# module-basic-ui.net
KiCad netlist of a schematic drawn in EAGLE
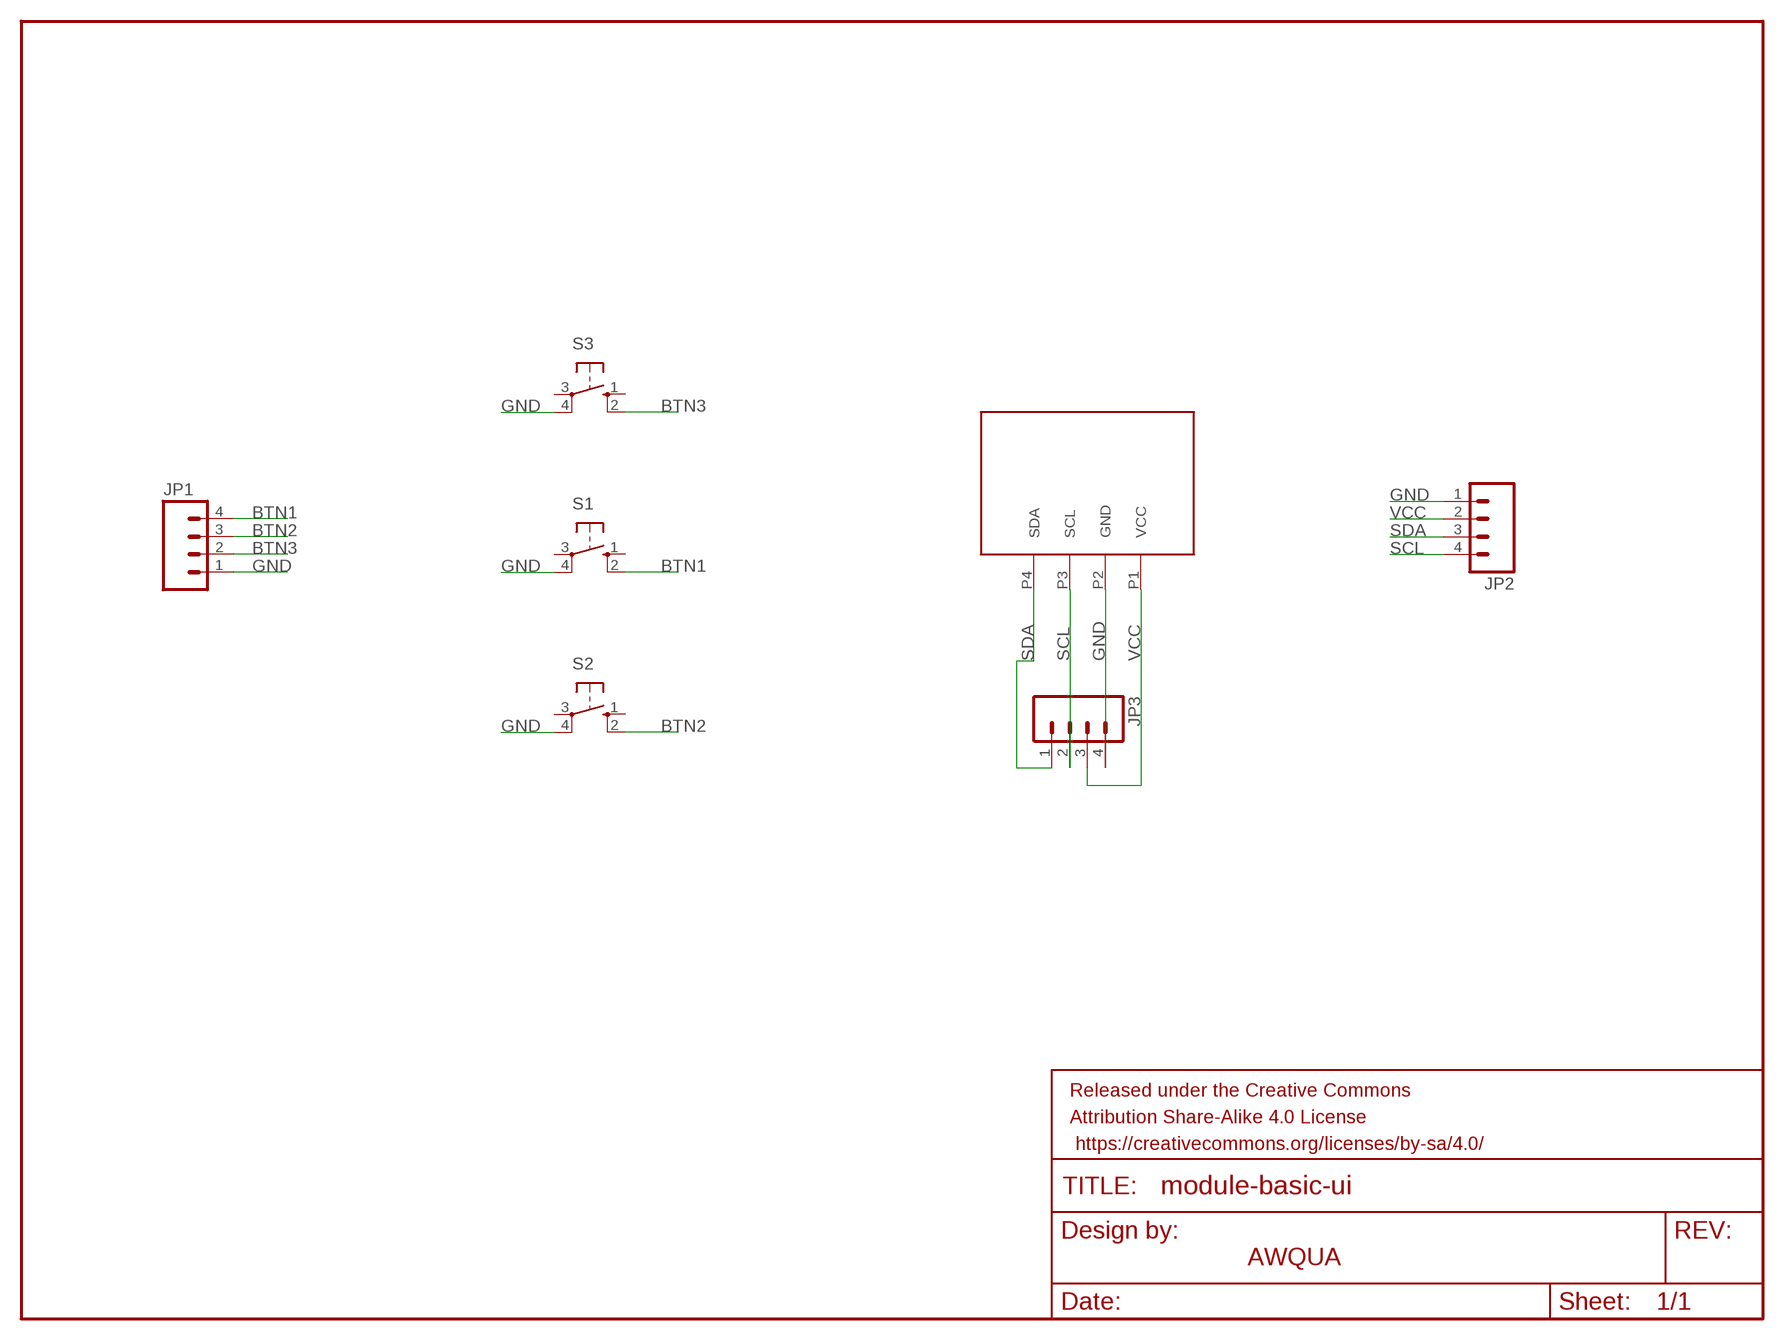
[diagram p0: schematic, sheet 1]

(export (version "E")
  (design (tool "Eeschema 10.0.6"))
  (components
    (comp (ref "FRAME1")
      (value "FRAME-LETTER")
      (footprint "eagle-import:CREATIVE_COMMONS")
      (libsource (lib "eagle-import") (part "FRAME-LETTER"))
    )
    (comp (ref "JP1")
      (value "M04PTH")
      (footprint "eagle-import:1X04")
      (libsource (lib "eagle-import") (part "M04PTH"))
    )
    (comp (ref "JP2")
      (value "M04PTH")
      (footprint "eagle-import:1X04")
      (libsource (lib "eagle-import") (part "M04PTH"))
    )
    (comp (ref "JP3")
      (value "M04PTH")
      (footprint "eagle-import:1X04")
      (libsource (lib "eagle-import") (part "M04PTH"))
    )
    (comp (ref "S1")
      (value "40-XX")
      (footprint "eagle-import:B3F-40XX")
      (fields (field (name "MF") "OMRON COMPONENTS USA") (field (name "MPN") "B3F-4000"))
      (libsource (lib "eagle-import") (part "40-XX"))
    )
    (comp (ref "S2")
      (value "40-XX")
      (footprint "eagle-import:B3F-40XX")
      (fields (field (name "MF") "OMRON COMPONENTS USA") (field (name "MPN") "B3F-4000"))
      (libsource (lib "eagle-import") (part "40-XX"))
    )
    (comp (ref "S3")
      (value "40-XX")
      (footprint "eagle-import:B3F-40XX")
      (fields (field (name "MF") "OMRON COMPONENTS USA") (field (name "MPN") "B3F-4000"))
      (libsource (lib "eagle-import") (part "40-XX"))
    )
    (comp (ref "U$2")
      (value "I2C-OLED-096")
      (footprint "eagle-import:I2C-OLED-096")
      (libsource (lib "eagle-import") (part "I2C-OLED-096"))
    )
  )
  (nets
    (net (code "1") (name "/BTN1") (class "Default")
      (node (ref "JP1") (pin "4") (pinfunction "4_4") (pintype "passive"))
      (node (ref "S1") (pin "2") (pinfunction "S1_2") (pintype "passive"))
    )
    (net (code "2") (name "/BTN2") (class "Default")
      (node (ref "JP1") (pin "3") (pinfunction "3_3") (pintype "passive"))
      (node (ref "S2") (pin "2") (pinfunction "S1_2") (pintype "passive"))
    )
    (net (code "3") (name "/BTN3") (class "Default")
      (node (ref "JP1") (pin "2") (pinfunction "2_2") (pintype "passive"))
      (node (ref "S3") (pin "2") (pinfunction "S1_2") (pintype "passive"))
    )
    (net (code "4") (name "/GND") (class "Default")
      (node (ref "JP1") (pin "1") (pinfunction "1_1") (pintype "passive"))
      (node (ref "JP2") (pin "1") (pinfunction "1_1") (pintype "passive"))
      (node (ref "JP3") (pin "4") (pinfunction "4_4") (pintype "passive"))
      (node (ref "S1") (pin "4") (pinfunction "P1_4") (pintype "passive"))
      (node (ref "S2") (pin "4") (pinfunction "P1_4") (pintype "passive"))
      (node (ref "S3") (pin "4") (pinfunction "P1_4") (pintype "passive"))
      (node (ref "U$2") (pin "P2") (pinfunction "GND_P2") (pintype "bidirectional"))
    )
    (net (code "5") (name "/SCL") (class "Default")
      (node (ref "JP2") (pin "4") (pinfunction "4_4") (pintype "passive"))
      (node (ref "JP3") (pin "2") (pinfunction "2_2") (pintype "passive"))
      (node (ref "U$2") (pin "P3") (pinfunction "SCL_P3") (pintype "bidirectional"))
    )
    (net (code "6") (name "/SDA") (class "Default")
      (node (ref "JP2") (pin "3") (pinfunction "3_3") (pintype "passive"))
      (node (ref "JP3") (pin "1") (pinfunction "1_1") (pintype "passive"))
      (node (ref "U$2") (pin "P4") (pinfunction "SDA_P4") (pintype "bidirectional"))
    )
    (net (code "7") (name "/VCC") (class "Default")
      (node (ref "JP2") (pin "2") (pinfunction "2_2") (pintype "passive"))
      (node (ref "JP3") (pin "3") (pinfunction "3_3") (pintype "passive"))
      (node (ref "U$2") (pin "P1") (pinfunction "VCC_P1") (pintype "bidirectional"))
    )
    (net (code "8") (name "unconnected-(S1-P-Pad3)") (class "Default")
      (node (ref "S1") (pin "3") (pinfunction "P_3") (pintype "passive"))
    )
    (net (code "9") (name "unconnected-(S1-S-Pad1)") (class "Default")
      (node (ref "S1") (pin "1") (pinfunction "S_1") (pintype "passive"))
    )
    (net (code "10") (name "unconnected-(S2-P-Pad3)") (class "Default")
      (node (ref "S2") (pin "3") (pinfunction "P_3") (pintype "passive"))
    )
    (net (code "11") (name "unconnected-(S2-S-Pad1)") (class "Default")
      (node (ref "S2") (pin "1") (pinfunction "S_1") (pintype "passive"))
    )
    (net (code "12") (name "unconnected-(S3-P-Pad3)") (class "Default")
      (node (ref "S3") (pin "3") (pinfunction "P_3") (pintype "passive"))
    )
    (net (code "13") (name "unconnected-(S3-S-Pad1)") (class "Default")
      (node (ref "S3") (pin "1") (pinfunction "S_1") (pintype "passive"))
    )
  )
)
